# 200_Peripherals_Sensors.net
KiCad netlist of a schematic drawn in Altium Designer
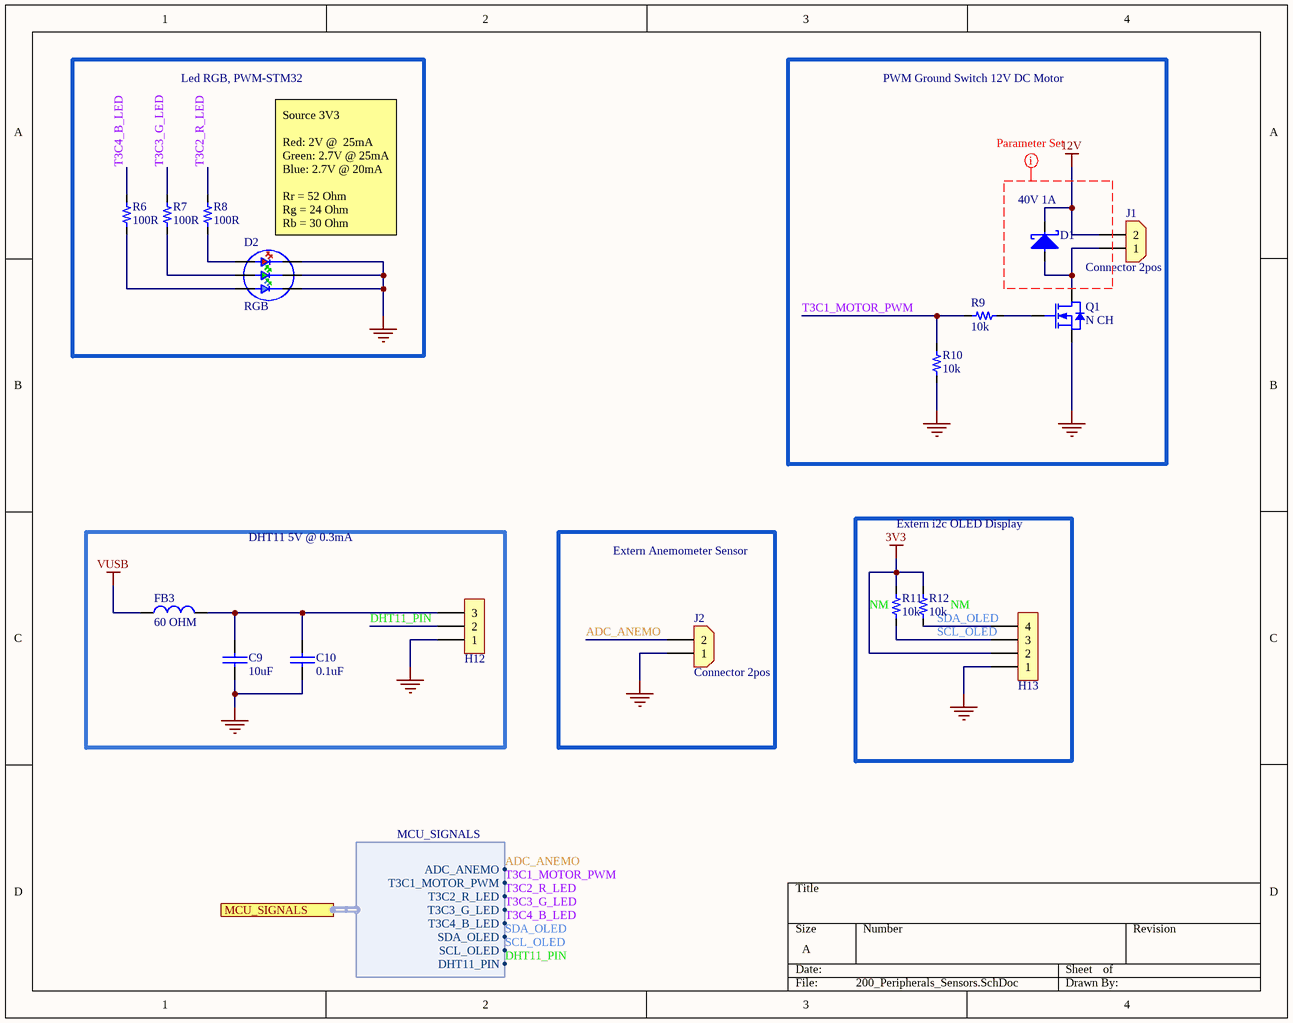
[diagram p0: 200_Peripherals_Sensors.SchDoc]

(export (version "E")
  (design (tool "Eeschema 10.0.6"))
  (components
    (comp (ref "C9")
      (value "10uF")
      (footprint "0805_cap")
      (description "25V 10uF X5R ±10% 0805 Multilayer Ceramic Capacitors MLCC - SMD/SMT ROHS")
      (fields
        (field (name "MANUFACTURER") "Samsung Electro-Mechanics")
        (field (name "MANUFACTURER PART NUMBER") "CL21A106KAYNNNE")
      )
      (libsource (lib "shared_lib") (part "Cap_10uF_0805_25V_"))
    )
    (comp (ref "C10")
      (value "0.1uF")
      (footprint "0603_cap")
      (description "50V 100nF Y5V -20%~+80% 0603 Multilayer Ceramic Capacitors MLCC - SMD/SMT ROHS")
      (fields
        (field (name "MANUFACTURER") "Walsin Tech Corp")
        (field (name "MANUFACTURER PART NUMBER") "0603F104Z500CT")
      )
      (libsource (lib "shared_lib") (part "Cap_0.1uF_0603_50V"))
    )
    (comp (ref "D1")
      (value "40V 1A")
      (footprint "SOD_123")
      (description "DIODE SCHOTTKY 40V 1A SOD123F")
      (fields
        (field (name "MANUFACTURER") "Shanghai Prisemi Elec")
        (field (name "MANUFACTURER PART NUMBER") "PSBD1DF40V1H")
      )
      (libsource (lib "shared_lib") (part "D_Schottky_40V_1A_SOD_123F"))
    )
    (comp (ref "D2")
      (value "RGB")
      (footprint "RGB_NS_3.5X3.7")
      (description "-30℃~+85℃ RGB 110° 3535(mm) Light Emitting Diodes (LED) ROHS")
      (fields
        (field (name "MANUFACTURER") "Foshan NationStar Optoelectronics")
        (field (name "MANUFACTURER PART NUMBER") "RS-3535MWAM")
      )
      (libsource (lib "shared_lib") (part "LED_RGB_3535_SMD"))
    )
    (comp (ref "FB3")
      (value "60 OHM")
      (footprint "0603_fb")
      (description "2A 1 100mΩ 60Ω@100MHz ±25% 0603 Ferrite Beads ROHS")
      (fields
        (field (name "MANUFACTURER") "TAI-TECH")
        (field (name "MANUFACTURER PART NUMBER") "HCB1608KF-600T20")
      )
      (libsource (lib "shared_lib") (part "FB_60_0603_2A"))
    )
    (comp (ref "H12")
      (value "3x1")
      (footprint "H_3X1_TH_100mil")
      (description "H_Male_3x1_TH_100mil")
      (libsource (lib "shared_lib") (part "H_Male_3x1_TH_100mil"))
    )
    (comp (ref "H13")
      (value "4x1")
      (footprint "H_4x1_TH_2.54mm")
      (description "H_Male_4x1_TH_100mil")
      (libsource (lib "shared_lib") (part "H_Male_4x1_TH_100mil"))
    )
    (comp (ref "J1")
      (value "Connector 2pos")
      (footprint "CON_2x1_TH_5MM")
      (description "2POS 5MM")
      (fields (field (name "MANUFACTURER") "JILN") (field (name "MANUFACTURER PART NUMBER") "JL126-50002G01"))
      (libsource (lib "shared_lib") (part "Con_2x1_TH_5mm"))
    )
    (comp (ref "J2")
      (value "Connector 2pos")
      (footprint "CON_2x1_TH_5MM")
      (description "2POS 5MM")
      (fields (field (name "MANUFACTURER") "JILN") (field (name "MANUFACTURER PART NUMBER") "JL126-50002G01"))
      (libsource (lib "shared_lib") (part "Con_2x1_TH_5mm"))
    )
    (comp (ref "Q1")
      (value "N CH")
      (footprint "SOT_23_3")
      (description "MOSFET N-CH 20V SOT23")
      (fields (field (name "MANUFACTURER") "Doeshare") (field (name "MANUFACTURER PART NUMBER") "DN2302S"))
      (libsource (lib "shared_lib") (part "Q_NFET_20V_3.2A_SOT23"))
    )
    (comp (ref "R6")
      (value "100R")
      (footprint "0603_res")
      (description "RES SMD 100R OHM 5% 1/10W 0603")
      (fields
        (field (name "MANUFACTURER") "FOJAN")
        (field (name "MANUFACTURER PART NUMBER") "FRC0603J101 TS")
      )
      (libsource (lib "shared_lib") (part "Res_100R_0603_1/10W"))
    )
    (comp (ref "R7")
      (value "100R")
      (footprint "0603_res")
      (description "RES SMD 100R OHM 5% 1/10W 0603")
      (fields
        (field (name "MANUFACTURER") "FOJAN")
        (field (name "MANUFACTURER PART NUMBER") "FRC0603J101 TS")
      )
      (libsource (lib "shared_lib") (part "Res_100R_0603_1/10W"))
    )
    (comp (ref "R8")
      (value "100R")
      (footprint "0603_res")
      (description "RES SMD 100R OHM 5% 1/10W 0603")
      (fields
        (field (name "MANUFACTURER") "FOJAN")
        (field (name "MANUFACTURER PART NUMBER") "FRC0603J101 TS")
      )
      (libsource (lib "shared_lib") (part "Res_100R_0603_1/10W"))
    )
    (comp (ref "R9")
      (value "10k")
      (footprint "0603_res")
      (description "RES SMD 10k OHM 5% 1/10W 0603")
      (fields (field (name "MANUFACTURER") "FOJAN") (field (name "MANUFACTURER PART NUMBER") "FRC0603J103TS"))
      (libsource (lib "shared_lib") (part "Res_10k_0603_1/10W"))
    )
    (comp (ref "R10")
      (value "10k")
      (footprint "0603_res")
      (description "RES SMD 10k OHM 5% 1/10W 0603")
      (fields (field (name "MANUFACTURER") "FOJAN") (field (name "MANUFACTURER PART NUMBER") "FRC0603J103TS"))
      (libsource (lib "shared_lib") (part "Res_10k_0603_1/10W"))
    )
    (comp (ref "R11")
      (value "10k")
      (footprint "0603_res")
      (description "RES SMD 10k OHM 5% 1/10W 0603")
      (fields
        (field (name "USAGE") "NM")
        (field (name "MANUFACTURER") "FOJAN")
        (field (name "MANUFACTURER PART NUMBER") "FRC0603J103TS")
      )
      (libsource (lib "shared_lib") (part "Res_10k_0603_1/10W"))
    )
    (comp (ref "R12")
      (value "10k")
      (footprint "0603_res")
      (description "RES SMD 10k OHM 5% 1/10W 0603")
      (fields
        (field (name "USAGE") "NM")
        (field (name "MANUFACTURER") "FOJAN")
        (field (name "MANUFACTURER PART NUMBER") "FRC0603J103TS")
      )
      (libsource (lib "shared_lib") (part "Res_10k_0603_1/10W"))
    )
  )
  (nets
    (net (code "2") (name "/ADC_ANEMO") (class "Default")
      (node (ref "J2") (pin "2") (pinfunction "2_2") (pintype "passive"))
    )
    (net (code "3") (name "/DHT11_PIN") (class "Default")
      (node (ref "H12") (pin "2") (pinfunction "2_2") (pintype "passive"))
    )
    (net (code "4") (name "/SCL_OLED") (class "Default")
      (node (ref "H13") (pin "3") (pinfunction "3_3") (pintype "passive"))
      (node (ref "R11") (pin "1") (pinfunction "1_1") (pintype "passive"))
    )
    (net (code "5") (name "/SDA_OLED") (class "Default")
      (node (ref "H13") (pin "4") (pinfunction "4_4") (pintype "passive"))
      (node (ref "R12") (pin "1") (pinfunction "1_1") (pintype "passive"))
    )
    (net (code "6") (name "/T3C1_MOTOR_PWM") (class "Default")
      (node (ref "R10") (pin "2") (pinfunction "2_2") (pintype "passive"))
      (node (ref "R9") (pin "2") (pinfunction "2_2") (pintype "passive"))
    )
    (net (code "7") (name "/T3C2_R_LED") (class "Default")
      (node (ref "R8") (pin "2") (pinfunction "2_2") (pintype "passive"))
    )
    (net (code "8") (name "/T3C3_G_LED") (class "Default")
      (node (ref "R7") (pin "2") (pinfunction "2_2") (pintype "passive"))
    )
    (net (code "9") (name "/T3C4_B_LED") (class "Default")
      (node (ref "R6") (pin "2") (pinfunction "2_2") (pintype "passive"))
    )
    (net (code "11") (name "3V3") (class "Default")
      (node (ref "H13") (pin "2") (pinfunction "2_2") (pintype "passive"))
      (node (ref "R11") (pin "2") (pinfunction "2_2") (pintype "passive"))
      (node (ref "R12") (pin "2") (pinfunction "2_2") (pintype "passive"))
    )
    (net (code "12") (name "12V") (class "Default")
      (node (ref "D1") (pin "1") (pinfunction "1_1") (pintype "passive"))
      (node (ref "J1") (pin "2") (pinfunction "2_2") (pintype "passive"))
    )
    (net (code "13") (name "GND") (class "Default")
      (node (ref "C10") (pin "2") (pinfunction "2_2") (pintype "passive"))
      (node (ref "C9") (pin "2") (pinfunction "2_2") (pintype "passive"))
      (node (ref "D2") (pin "1") (pinfunction "1_1") (pintype "passive"))
      (node (ref "D2") (pin "2") (pinfunction "2_2") (pintype "passive"))
      (node (ref "D2") (pin "3") (pinfunction "3_3") (pintype "passive"))
      (node (ref "H12") (pin "1") (pinfunction "1_1") (pintype "passive"))
      (node (ref "H13") (pin "1") (pinfunction "1_1") (pintype "passive"))
      (node (ref "J2") (pin "1") (pinfunction "1_1") (pintype "passive"))
      (node (ref "Q1") (pin "2") (pinfunction "S_2") (pintype "passive"))
      (node (ref "R10") (pin "1") (pinfunction "1_1") (pintype "passive"))
    )
    (net (code "14") (name "Net-(C10-Pad1)") (class "Default")
      (node (ref "C10") (pin "1") (pinfunction "1_1") (pintype "passive"))
      (node (ref "C9") (pin "1") (pinfunction "1_1") (pintype "passive"))
      (node (ref "FB3") (pin "2") (pinfunction "2_2") (pintype "passive"))
      (node (ref "H12") (pin "3") (pinfunction "3_3") (pintype "passive"))
    )
    (net (code "15") (name "Net-(D2-Pad4)") (class "Default")
      (node (ref "D2") (pin "4") (pinfunction "4_4") (pintype "passive"))
      (node (ref "R8") (pin "1") (pinfunction "1_1") (pintype "passive"))
    )
    (net (code "16") (name "Net-(D2-Pad5)") (class "Default")
      (node (ref "D2") (pin "5") (pinfunction "5_5") (pintype "passive"))
      (node (ref "R7") (pin "1") (pinfunction "1_1") (pintype "passive"))
    )
    (net (code "17") (name "Net-(D2-Pad6)") (class "Default")
      (node (ref "D2") (pin "6") (pinfunction "6_6") (pintype "passive"))
      (node (ref "R6") (pin "1") (pinfunction "1_1") (pintype "passive"))
    )
    (net (code "18") (name "Net-(Q1-D)") (class "Default")
      (node (ref "D1") (pin "2") (pinfunction "2_2") (pintype "passive"))
      (node (ref "J1") (pin "1") (pinfunction "1_1") (pintype "passive"))
      (node (ref "Q1") (pin "3") (pinfunction "D_3") (pintype "passive"))
    )
    (net (code "19") (name "Net-(Q1-G)") (class "Default")
      (node (ref "Q1") (pin "1") (pinfunction "G_1") (pintype "passive"))
      (node (ref "R9") (pin "1") (pinfunction "1_1") (pintype "passive"))
    )
    (net (code "20") (name "VUSB") (class "Default")
      (node (ref "FB3") (pin "1") (pinfunction "1_1") (pintype "passive"))
    )
  )
)
